# Sheet1.net
KiCad netlist of a schematic drawn in Altium Designer
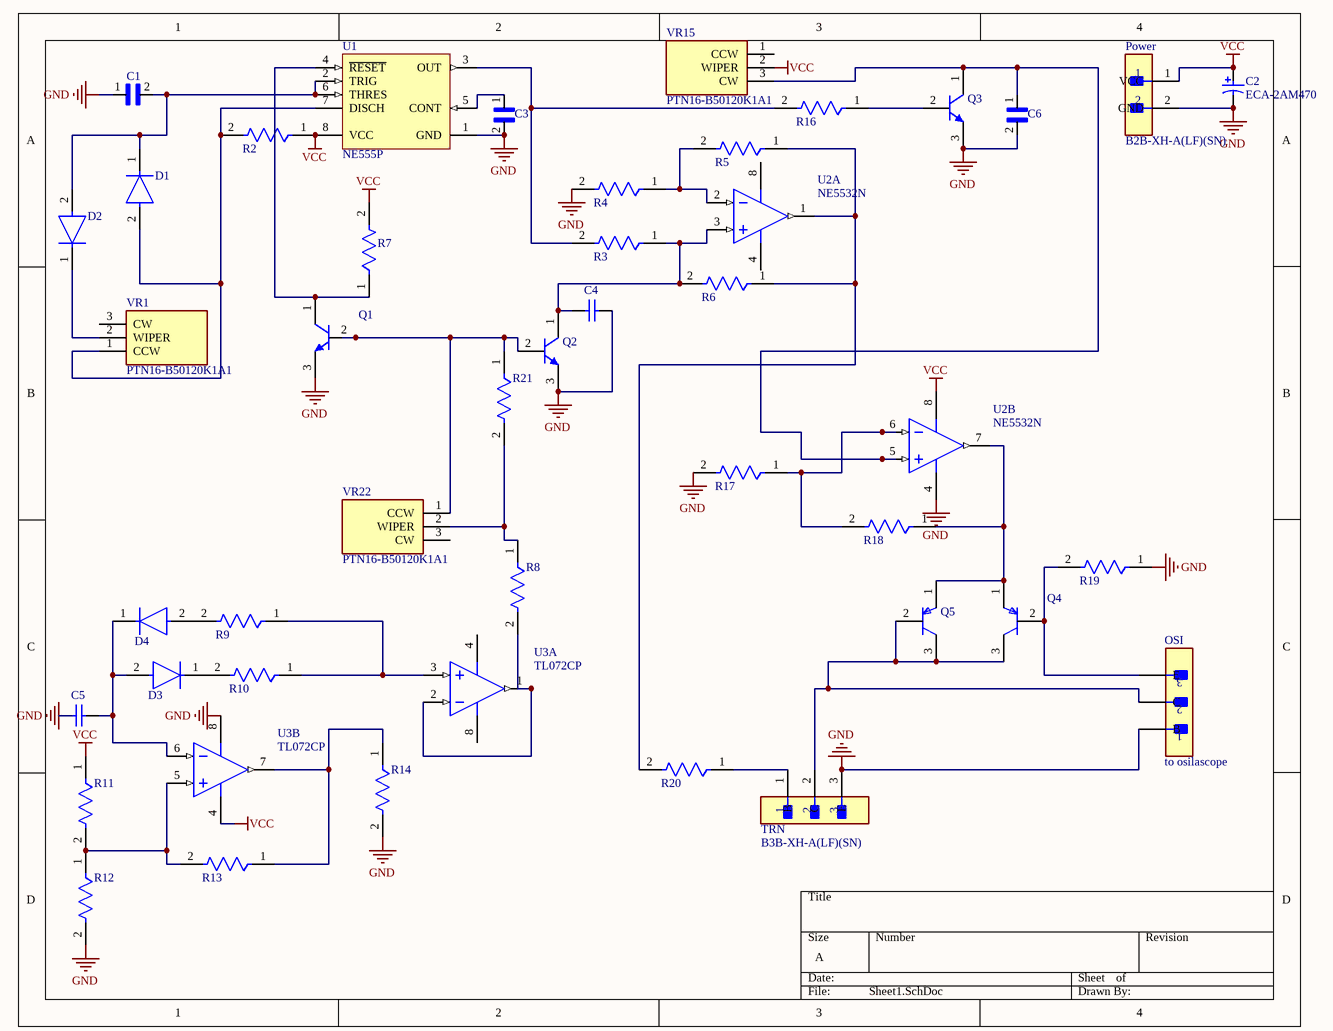
[diagram p0: Sheet1.SchDoc]

(export (version "E")
  (design (tool "Eeschema 10.0.6"))
  (components
    (comp (ref "C1")
      (value "FG24X7R1A106KRT00")
      (footprint "CAPRB500W50L450T300H550")
      (description "10 ÂµF Â±10% 10V Ceramic Capacitor X7R Radial")
      (fields (field (name "MF") "TDK"))
      (libsource (lib "") (part "FG24X7R1A106KRT00_1"))
    )
    (comp (ref "C2")
      (value "ECA-2AM470")
      (footprint "CAPPR65-350-1150X800X1250")
      (description "Aluminum Electrolytic Capacitor, 47 uF, +/- 20%, 100 V, -40 to 85 degC, 2-Pin THD, RoHS, Bulk")
      (libsource (lib "Altium Content Vault") (part "CAP-P-2"))
    )
    (comp (ref "C3")
      (value "FG24X7R1A106KRT00")
      (footprint "CAPRB500W50L450T300H550")
      (description "10 ÂµF Â±10% 10V Ceramic Capacitor X7R Radial")
      (fields (field (name "MF") "TDK"))
      (libsource (lib "FG24X7R1A106KRT00") (part "FG24X7R1A106KRT00"))
    )
    (comp (ref "C4")
      (value "SA115C104KAR")
      (footprint "AVX-SA115C104KAR")
      (fields (field (name "TOLERANCE") "±10%") (field (name "MANUFACTURER") "AVX"))
      (libsource (lib "Altium Content Vault") (part "CAP-NP-2"))
    )
    (comp (ref "C5")
      (value "SA115C104KAR")
      (footprint "AVX-SA115C104KAR")
      (fields (field (name "TOLERANCE") "±10%") (field (name "MANUFACTURER") "AVX"))
      (libsource (lib "Altium Content Vault") (part "CAP-NP-2"))
    )
    (comp (ref "C6")
      (value "FG24X7R1A106KRT00")
      (footprint "CAPRB500W50L450T300H550")
      (description "10 ÂµF Â±10% 10V Ceramic Capacitor X7R Radial")
      (fields (field (name "MF") "TDK"))
      (libsource (lib "FG24X7R1A106KRT00") (part "FG24X7R1A106KRT00"))
    )
    (comp (ref "D1")
      (value "1N4001-E3/54")
      (footprint "FP-1N4001-E3-54-MFG")
      (description "DIODE GEN PURP 50V 1A DO204AL")
      (fields (field (name "VOLTAGE") "50V"))
      (libsource (lib "Altium Content Vault") (part "d7152d700b627762746794eb795d46e"))
    )
    (comp (ref "D2")
      (value "1N4001-E3/54")
      (footprint "FP-1N4001-E3-54-MFG")
      (description "DIODE GEN PURP 50V 1A DO204AL")
      (fields (field (name "VOLTAGE") "50V"))
      (libsource (lib "Altium Content Vault") (part "d7152d700b627762746794eb795d46e"))
    )
    (comp (ref "D3")
      (value "1N4001-E3/54")
      (footprint "FP-1N4001-E3-54-MFG")
      (description "DIODE GEN PURP 50V 1A DO204AL")
      (fields (field (name "VOLTAGE") "50V"))
      (libsource (lib "Altium Content Vault") (part "d7152d700b627762746794eb795d46e"))
    )
    (comp (ref "D4")
      (value "1N4001-E3/54")
      (footprint "FP-1N4001-E3-54-MFG")
      (description "DIODE GEN PURP 50V 1A DO204AL")
      (fields (field (name "VOLTAGE") "50V"))
      (libsource (lib "Altium Content Vault") (part "d7152d700b627762746794eb795d46e"))
    )
    (comp (ref "OSI")
      (value "to osilascope")
      (footprint "FP-B3B-XH-A_LF_SN-MFG")
      (description "CONN HEADER VERT 3POS 2.5MM")
      (libsource (lib "Altium Content Vault") (part "0d3f023dd272f625e17a2be33dea85f"))
    )
    (comp (ref "Power")
      (value "B2B-XH-A(LF)(SN)")
      (footprint "FP-B2B-XH-A_LF_SN-MFG")
      (description "CONN HEADER VERT 2POS 2.5MM")
      (libsource (lib "Altium Content Vault") (part "3bc925449376181038e59eaffc5286c"))
    )
    (comp (ref "Q1")
      (value "P2N2222ARL1G")
      (footprint "ONSC-TO-92-3-29-11_AM_BL")
      (description "Amplifier Transistor, NPN Silicon, 3-Pin TO-92, Pb-Free, Tape and Reel")
      (fields (field (name "MANUFACTURER") "On Semiconductor"))
      (libsource (lib "Altium Content Vault") (part "ONSC-NPN-C1B2E3-3"))
    )
    (comp (ref "Q2")
      (value "P2N2222ARL1G")
      (footprint "ONSC-TO-92-3-29-11_AM_BL")
      (description "Amplifier Transistor, NPN Silicon, 3-Pin TO-92, Pb-Free, Tape and Reel")
      (fields (field (name "MANUFACTURER") "On Semiconductor"))
      (libsource (lib "Altium Content Vault") (part "ONSC-NPN-C1B2E3-3"))
    )
    (comp (ref "Q3")
      (value "P2N2222ARL1G")
      (footprint "ONSC-TO-92-3-29-11_AM_BL")
      (description "Amplifier Transistor, NPN Silicon, 3-Pin TO-92, Pb-Free, Tape and Reel")
      (fields (field (name "MANUFACTURER") "On Semiconductor"))
      (libsource (lib "Altium Content Vault") (part "ONSC-NPN-C1B2E3-3"))
    )
    (comp (ref "Q4")
      (value "2N3906TF")
      (footprint "FP-135AR-MFG")
      (description "2N3906TF Small Signal Bipolar Transistor, 0.2A I(C), 40V V(BR)CEO, 1-Element, PNP, Silicon, TO-92")
      (libsource (lib "Altium Content Vault") (part "40d2b7e180a7bcff784209620afba3e"))
    )
    (comp (ref "Q5")
      (value "2N3906TF")
      (footprint "FP-135AR-MFG")
      (description "2N3906TF Small Signal Bipolar Transistor, 0.2A I(C), 40V V(BR)CEO, 1-Element, PNP, Silicon, TO-92")
      (libsource (lib "Altium Content Vault") (part "40d2b7e180a7bcff784209620afba3e"))
    )
    (comp (ref "R2")
      (value "MRS16000C2002FCT00")
      (footprint "FP-MRS1600-MFG")
      (description "RES 20K OHM 0.4W 1% AXIAL")
      (fields (field (name "TOLERANCE") "1%"))
      (libsource (lib "Altium Content Vault") (part "1029c3af85768c4190bb7ad29bc67b5"))
    )
    (comp (ref "R3")
      (value "MRS16000C2002FCT00")
      (footprint "FP-MRS1600-MFG")
      (description "RES 20K OHM 0.4W 1% AXIAL")
      (fields (field (name "TOLERANCE") "1%"))
      (libsource (lib "Altium Content Vault") (part "1029c3af85768c4190bb7ad29bc67b5"))
    )
    (comp (ref "R4")
      (value "MRS16000C2002FCT00")
      (footprint "FP-MRS1600-MFG")
      (description "RES 20K OHM 0.4W 1% AXIAL")
      (fields (field (name "TOLERANCE") "1%"))
      (libsource (lib "Altium Content Vault") (part "1029c3af85768c4190bb7ad29bc67b5"))
    )
    (comp (ref "R5")
      (value "MRS16000C2002FCT00")
      (footprint "FP-MRS1600-MFG")
      (description "RES 20K OHM 0.4W 1% AXIAL")
      (fields (field (name "TOLERANCE") "1%"))
      (libsource (lib "Altium Content Vault") (part "1029c3af85768c4190bb7ad29bc67b5"))
    )
    (comp (ref "R6")
      (value "MRS16000C2002FCT00")
      (footprint "FP-MRS1600-MFG")
      (description "RES 20K OHM 0.4W 1% AXIAL")
      (fields (field (name "TOLERANCE") "1%"))
      (libsource (lib "Altium Content Vault") (part "1029c3af85768c4190bb7ad29bc67b5"))
    )
    (comp (ref "R7")
      (value "MRS16000C2002FCT00")
      (footprint "FP-MRS1600-MFG")
      (description "RES 20K OHM 0.4W 1% AXIAL")
      (fields (field (name "TOLERANCE") "1%"))
      (libsource (lib "Altium Content Vault") (part "1029c3af85768c4190bb7ad29bc67b5"))
    )
    (comp (ref "R8")
      (value "MRS16000C2002FCT00")
      (footprint "FP-MRS1600-MFG")
      (description "RES 20K OHM 0.4W 1% AXIAL")
      (fields (field (name "TOLERANCE") "1%"))
      (libsource (lib "Altium Content Vault") (part "1029c3af85768c4190bb7ad29bc67b5"))
    )
    (comp (ref "R9")
      (value "MRS16000C2002FCT00")
      (footprint "FP-MRS1600-MFG")
      (description "RES 20K OHM 0.4W 1% AXIAL")
      (fields (field (name "TOLERANCE") "1%"))
      (libsource (lib "Altium Content Vault") (part "1029c3af85768c4190bb7ad29bc67b5"))
    )
    (comp (ref "R10")
      (value "MRS16000C2002FCT00")
      (footprint "FP-MRS1600-MFG")
      (description "RES 20K OHM 0.4W 1% AXIAL")
      (fields (field (name "TOLERANCE") "1%"))
      (libsource (lib "Altium Content Vault") (part "1029c3af85768c4190bb7ad29bc67b5"))
    )
    (comp (ref "R11")
      (value "MRS16000C2002FCT00")
      (footprint "FP-MRS1600-MFG")
      (description "RES 20K OHM 0.4W 1% AXIAL")
      (fields (field (name "TOLERANCE") "1%"))
      (libsource (lib "Altium Content Vault") (part "1029c3af85768c4190bb7ad29bc67b5"))
    )
    (comp (ref "R12")
      (value "MRS16000C2002FCT00")
      (footprint "FP-MRS1600-MFG")
      (description "RES 20K OHM 0.4W 1% AXIAL")
      (fields (field (name "TOLERANCE") "1%"))
      (libsource (lib "Altium Content Vault") (part "1029c3af85768c4190bb7ad29bc67b5"))
    )
    (comp (ref "R13")
      (value "MRS16000C2002FCT00")
      (footprint "FP-MRS1600-MFG")
      (description "RES 20K OHM 0.4W 1% AXIAL")
      (fields (field (name "TOLERANCE") "1%"))
      (libsource (lib "Altium Content Vault") (part "1029c3af85768c4190bb7ad29bc67b5"))
    )
    (comp (ref "R14")
      (value "MRS16000C2002FCT00")
      (footprint "FP-MRS1600-MFG")
      (description "RES 20K OHM 0.4W 1% AXIAL")
      (fields (field (name "TOLERANCE") "1%"))
      (libsource (lib "Altium Content Vault") (part "1029c3af85768c4190bb7ad29bc67b5"))
    )
    (comp (ref "R16")
      (value "MRS16000C2002FCT00")
      (footprint "FP-MRS1600-MFG")
      (description "RES 20K OHM 0.4W 1% AXIAL")
      (fields (field (name "TOLERANCE") "1%"))
      (libsource (lib "Altium Content Vault") (part "1029c3af85768c4190bb7ad29bc67b5"))
    )
    (comp (ref "R17")
      (value "MRS16000C2002FCT00")
      (footprint "FP-MRS1600-MFG")
      (description "RES 20K OHM 0.4W 1% AXIAL")
      (fields (field (name "TOLERANCE") "1%"))
      (libsource (lib "Altium Content Vault") (part "1029c3af85768c4190bb7ad29bc67b5"))
    )
    (comp (ref "R18")
      (value "MRS16000C2002FCT00")
      (footprint "FP-MRS1600-MFG")
      (description "RES 20K OHM 0.4W 1% AXIAL")
      (fields (field (name "TOLERANCE") "1%"))
      (libsource (lib "Altium Content Vault") (part "1029c3af85768c4190bb7ad29bc67b5"))
    )
    (comp (ref "R19")
      (value "MRS16000C2002FCT00")
      (footprint "FP-MRS1600-MFG")
      (description "RES 20K OHM 0.4W 1% AXIAL")
      (fields (field (name "TOLERANCE") "1%"))
      (libsource (lib "Altium Content Vault") (part "1029c3af85768c4190bb7ad29bc67b5"))
    )
    (comp (ref "R20")
      (value "MRS16000C2002FCT00")
      (footprint "FP-MRS1600-MFG")
      (description "RES 20K OHM 0.4W 1% AXIAL")
      (fields (field (name "TOLERANCE") "1%"))
      (libsource (lib "Altium Content Vault") (part "1029c3af85768c4190bb7ad29bc67b5"))
    )
    (comp (ref "R21")
      (value "MRS16000C2002FCT00")
      (footprint "FP-MRS1600-MFG")
      (description "RES 20K OHM 0.4W 1% AXIAL")
      (fields (field (name "TOLERANCE") "1%"))
      (libsource (lib "Altium Content Vault") (part "1029c3af85768c4190bb7ad29bc67b5"))
    )
    (comp (ref "TRN")
      (value "B3B-XH-A(LF)(SN)")
      (footprint "FP-B3B-XH-A_LF_SN-MFG")
      (description "CONN HEADER VERT 3POS 2.5MM")
      (libsource (lib "") (part "0d3f023dd272f625e17a2be33dea85f_1"))
    )
    (comp (ref "U1")
      (value "NE555P")
      (footprint "P0008A")
      (description "Precision Timer, 4.5 to 16 V, 0 to 70 degC, 8-Pin DIP, Pb-Free, Tube")
      (fields (field (name "MANUFACTURER") "TexasInstruments"))
      (libsource (lib "Altium Content Vault") (part "TI-NE555-P8"))
    )
    (comp (ref "U2")
      (value "NE5532N")
      (footprint "ONSC-PDIP-8-626-05")
      (fields (field (name "MANUFACTURER") "On Semiconductor"))
      (libsource (lib "Altium Content Vault") (part "ONSC-NE5532-PDIP-8-626-05"))
    )
    (comp (ref "U3")
      (value "TL072CP")
      (footprint "P0008A")
      (fields (field (name "MANUFACTURER") "Texas Instruments"))
      (libsource (lib "Altium Content Vault") (part "TI-AMP-D6-2-8_D"))
    )
    (comp (ref "VR1")
      (value "PTN16-B50120K1A1")
      (footprint "SamacSys:PTN16B50120K1A1")
      (description "Variable Resistor")
      (libsource (lib "") (part "PTN16-B50120K1A1_1"))
    )
    (comp (ref "VR15")
      (value "PTN16-B50120K1A1")
      (footprint "SamacSys:PTN16B50120K1A1")
      (description "Variable Resistor")
      (libsource (lib "*") (part "PTN16-B50120K1A1"))
    )
    (comp (ref "VR22")
      (value "PTN16-B50120K1A1")
      (footprint "SamacSys:PTN16B50120K1A1")
      (description "Variable Resistor")
      (libsource (lib "*") (part "PTN16-B50120K1A1"))
    )
  )
  (nets
    (net (code "1") (name "GND") (class "Default")
      (node (ref "C1") (pin "1") (pinfunction "1_1") (pintype "passive"))
      (node (ref "C2") (pin "2") (pinfunction "2_2") (pintype "passive"))
      (node (ref "C3") (pin "2") (pinfunction "2_2") (pintype "passive"))
      (node (ref "C4") (pin "2") (pinfunction "2_2") (pintype "passive"))
      (node (ref "C5") (pin "1") (pinfunction "1_1") (pintype "passive"))
      (node (ref "C6") (pin "2") (pinfunction "2_2") (pintype "passive"))
      (node (ref "OSI") (pin "1") (pinfunction "B_1") (pintype "passive"))
      (node (ref "Power") (pin "2") (pinfunction "GND_2") (pintype "passive"))
      (node (ref "Q1") (pin "3") (pinfunction "E_3") (pintype "passive"))
      (node (ref "Q2") (pin "3") (pinfunction "E_3") (pintype "passive"))
      (node (ref "Q3") (pin "3") (pinfunction "E_3") (pintype "passive"))
      (node (ref "R12") (pin "2") (pinfunction "2_2") (pintype "passive"))
      (node (ref "R14") (pin "2") (pinfunction "2_2") (pintype "passive"))
      (node (ref "R17") (pin "2") (pinfunction "2_2") (pintype "passive"))
      (node (ref "R19") (pin "1") (pinfunction "1_1") (pintype "passive"))
      (node (ref "R4") (pin "2") (pinfunction "2_2") (pintype "passive"))
      (node (ref "TRN") (pin "3") (pinfunction "E_3") (pintype "passive"))
      (node (ref "U1") (pin "1") (pinfunction "GND_1") (pintype "power_in"))
      (node (ref "U2") (pin "4") (pinfunction "V-_4") (pintype "power_in"))
      (node (ref "U3") (pin "8") (pinfunction "VCC+_8") (pintype "power_in"))
    )
    (net (code "2") (name "Net-(D1-A)") (class "Default")
      (node (ref "D1") (pin "2") (pinfunction "A_2") (pintype "passive"))
      (node (ref "R2") (pin "2") (pinfunction "2_2") (pintype "passive"))
      (node (ref "U1") (pin "7") (pinfunction "DISCH_7") (pintype "open_collector"))
      (node (ref "VR1") (pin "1") (pinfunction "CCW_1") (pintype "passive"))
    )
    (net (code "3") (name "Net-(D1-C)") (class "Default")
      (node (ref "C1") (pin "2") (pinfunction "2_2") (pintype "passive"))
      (node (ref "D1") (pin "1") (pinfunction "C_1") (pintype "passive"))
      (node (ref "D2") (pin "2") (pinfunction "A_2") (pintype "passive"))
      (node (ref "U1") (pin "2") (pinfunction "TRIG_2") (pintype "input"))
      (node (ref "U1") (pin "6") (pinfunction "THRES_6") (pintype "input"))
    )
    (net (code "4") (name "Net-(D2-C)") (class "Default")
      (node (ref "D2") (pin "1") (pinfunction "C_1") (pintype "passive"))
      (node (ref "VR1") (pin "2") (pinfunction "WIPER_2") (pintype "passive"))
    )
    (net (code "5") (name "Net-(D3-A)") (class "Default")
      (node (ref "C5") (pin "2") (pinfunction "2_2") (pintype "passive"))
      (node (ref "D3") (pin "2") (pinfunction "A_2") (pintype "passive"))
      (node (ref "D4") (pin "1") (pinfunction "C_1") (pintype "passive"))
      (node (ref "U3") (pin "6") (pinfunction "IN2-_6") (pintype "input"))
    )
    (net (code "6") (name "Net-(D3-C)") (class "Default")
      (node (ref "D3") (pin "1") (pinfunction "C_1") (pintype "passive"))
      (node (ref "R10") (pin "2") (pinfunction "2_2") (pintype "passive"))
    )
    (net (code "7") (name "Net-(D4-A)") (class "Default")
      (node (ref "D4") (pin "2") (pinfunction "A_2") (pintype "passive"))
      (node (ref "R9") (pin "2") (pinfunction "2_2") (pintype "passive"))
    )
    (net (code "8") (name "Net-(OSI-C)") (class "Default")
      (node (ref "OSI") (pin "2") (pinfunction "C_2") (pintype "passive"))
      (node (ref "Q4") (pin "3") (pinfunction "C_3") (pintype "passive"))
      (node (ref "Q5") (pin "2") (pinfunction "B_2") (pintype "passive"))
      (node (ref "Q5") (pin "3") (pinfunction "C_3") (pintype "passive"))
      (node (ref "TRN") (pin "2") (pinfunction "C_2") (pintype "passive"))
    )
    (net (code "9") (name "Net-(OSI-E)") (class "Default")
      (node (ref "OSI") (pin "3") (pinfunction "E_3") (pintype "passive"))
      (node (ref "Q4") (pin "2") (pinfunction "B_2") (pintype "passive"))
      (node (ref "R19") (pin "2") (pinfunction "2_2") (pintype "passive"))
    )
    (net (code "10") (name "Net-(Q1-B)") (class "Default")
      (node (ref "Q1") (pin "2") (pinfunction "B_2") (pintype "passive"))
      (node (ref "Q2") (pin "2") (pinfunction "B_2") (pintype "passive"))
      (node (ref "R21") (pin "1") (pinfunction "1_1") (pintype "passive"))
      (node (ref "VR22") (pin "1") (pinfunction "CCW_1") (pintype "passive"))
    )
    (net (code "11") (name "Net-(Q1-C)") (class "Default")
      (node (ref "Q1") (pin "1") (pinfunction "C_1") (pintype "passive"))
      (node (ref "R7") (pin "1") (pinfunction "1_1") (pintype "passive"))
      (node (ref "U1") (pin "4") (pinfunction "~{RESET}_4") (pintype "input"))
    )
    (net (code "12") (name "Net-(Q2-C)") (class "Default")
      (node (ref "C4") (pin "1") (pinfunction "1_1") (pintype "passive"))
      (node (ref "Q2") (pin "1") (pinfunction "C_1") (pintype "passive"))
      (node (ref "R3") (pin "1") (pinfunction "1_1") (pintype "passive"))
      (node (ref "R6") (pin "2") (pinfunction "2_2") (pintype "passive"))
      (node (ref "U2") (pin "3") (pinfunction "INA+_3") (pintype "input"))
    )
    (net (code "13") (name "Net-(Q3-B)") (class "Default")
      (node (ref "Q3") (pin "2") (pinfunction "B_2") (pintype "passive"))
      (node (ref "R16") (pin "1") (pinfunction "1_1") (pintype "passive"))
    )
    (net (code "14") (name "Net-(Q3-C)") (class "Default")
      (node (ref "C6") (pin "1") (pinfunction "1_1") (pintype "passive"))
      (node (ref "Q3") (pin "1") (pinfunction "C_1") (pintype "passive"))
      (node (ref "U2") (pin "5") (pinfunction "INB+_5") (pintype "input"))
      (node (ref "VR15") (pin "3") (pinfunction "CW_3") (pintype "passive"))
    )
    (net (code "15") (name "Net-(Q4-E)") (class "Default")
      (node (ref "Q4") (pin "1") (pinfunction "E_1") (pintype "passive"))
      (node (ref "Q5") (pin "1") (pinfunction "E_1") (pintype "passive"))
      (node (ref "R18") (pin "1") (pinfunction "1_1") (pintype "passive"))
      (node (ref "U2") (pin "7") (pinfunction "OUTB_7") (pintype "output"))
    )
    (net (code "16") (name "Net-(TRN-B)") (class "Default")
      (node (ref "R20") (pin "1") (pinfunction "1_1") (pintype "passive"))
      (node (ref "TRN") (pin "1") (pinfunction "B_1") (pintype "passive"))
    )
    (net (code "17") (name "Net-(U1-CONT)") (class "Default")
      (node (ref "C3") (pin "1") (pinfunction "1_1") (pintype "passive"))
      (node (ref "U1") (pin "5") (pinfunction "CONT_5") (pintype "input"))
    )
    (net (code "18") (name "Net-(U1-OUT)") (class "Default")
      (node (ref "R16") (pin "2") (pinfunction "2_2") (pintype "passive"))
      (node (ref "R3") (pin "2") (pinfunction "2_2") (pintype "passive"))
      (node (ref "U1") (pin "3") (pinfunction "OUT_3") (pintype "output"))
    )
    (net (code "19") (name "Net-(U2A-INA-)") (class "Default")
      (node (ref "R4") (pin "1") (pinfunction "1_1") (pintype "passive"))
      (node (ref "R5") (pin "2") (pinfunction "2_2") (pintype "passive"))
      (node (ref "U2") (pin "2") (pinfunction "INA-_2") (pintype "input"))
    )
    (net (code "20") (name "Net-(U2A-OUTA)") (class "Default")
      (node (ref "R20") (pin "2") (pinfunction "2_2") (pintype "passive"))
      (node (ref "R5") (pin "1") (pinfunction "1_1") (pintype "passive"))
      (node (ref "R6") (pin "1") (pinfunction "1_1") (pintype "passive"))
      (node (ref "U2") (pin "1") (pinfunction "OUTA_1") (pintype "output"))
    )
    (net (code "21") (name "Net-(U2B-INB-)") (class "Default")
      (node (ref "R17") (pin "1") (pinfunction "1_1") (pintype "passive"))
      (node (ref "R18") (pin "2") (pinfunction "2_2") (pintype "passive"))
      (node (ref "U2") (pin "6") (pinfunction "INB-_6") (pintype "input"))
    )
    (net (code "22") (name "Net-(U3A-IN1+)") (class "Default")
      (node (ref "R10") (pin "1") (pinfunction "1_1") (pintype "passive"))
      (node (ref "R9") (pin "1") (pinfunction "1_1") (pintype "passive"))
      (node (ref "U3") (pin "3") (pinfunction "IN1+_3") (pintype "input"))
    )
    (net (code "23") (name "Net-(U3A-IN1-)") (class "Default")
      (node (ref "R8") (pin "2") (pinfunction "2_2") (pintype "passive"))
      (node (ref "U3") (pin "1") (pinfunction "OUT1_1") (pintype "output"))
      (node (ref "U3") (pin "2") (pinfunction "IN1-_2") (pintype "input"))
    )
    (net (code "24") (name "Net-(U3B-IN2+)") (class "Default")
      (node (ref "R11") (pin "2") (pinfunction "2_2") (pintype "passive"))
      (node (ref "R12") (pin "1") (pinfunction "1_1") (pintype "passive"))
      (node (ref "R13") (pin "2") (pinfunction "2_2") (pintype "passive"))
      (node (ref "U3") (pin "5") (pinfunction "IN2+_5") (pintype "input"))
    )
    (net (code "25") (name "Net-(U3B-OUT2)") (class "Default")
      (node (ref "R13") (pin "1") (pinfunction "1_1") (pintype "passive"))
      (node (ref "R14") (pin "1") (pinfunction "1_1") (pintype "passive"))
      (node (ref "U3") (pin "7") (pinfunction "OUT2_7") (pintype "output"))
    )
    (net (code "26") (name "Net-(VR22-WIPER)") (class "Default")
      (node (ref "R21") (pin "2") (pinfunction "2_2") (pintype "passive"))
      (node (ref "R8") (pin "1") (pinfunction "1_1") (pintype "passive"))
      (node (ref "VR22") (pin "2") (pinfunction "WIPER_2") (pintype "passive"))
    )
    (net (code "27") (name "VCC") (class "Default")
      (node (ref "C2") (pin "1") (pinfunction "1_1") (pintype "passive"))
      (node (ref "Power") (pin "1") (pinfunction "VCC_1") (pintype "passive"))
      (node (ref "R11") (pin "1") (pinfunction "1_1") (pintype "passive"))
      (node (ref "R2") (pin "1") (pinfunction "1_1") (pintype "passive"))
      (node (ref "R7") (pin "2") (pinfunction "2_2") (pintype "passive"))
      (node (ref "U1") (pin "8") (pinfunction "VCC_8") (pintype "power_in"))
      (node (ref "U2") (pin "8") (pinfunction "V+_8") (pintype "power_in"))
      (node (ref "U3") (pin "4") (pinfunction "VCC-_4") (pintype "power_in"))
      (node (ref "VR15") (pin "2") (pinfunction "WIPER_2") (pintype "passive"))
    )
    (net (code "28") (name "unconnected-(U2A-V+-Pad8)") (class "Default")
      (node (ref "U2") (pin "8") (pinfunction "V+_8") (pintype "power_in"))
    )
    (net (code "29") (name "unconnected-(U2A-V--Pad4)") (class "Default")
      (node (ref "U2") (pin "4") (pinfunction "V-_4") (pintype "power_in"))
    )
    (net (code "30") (name "unconnected-(U3A-VCC+-Pad8)") (class "Default")
      (node (ref "U3") (pin "8") (pinfunction "VCC+_8") (pintype "power_in"))
    )
    (net (code "31") (name "unconnected-(U3A-VCC--Pad4)") (class "Default")
      (node (ref "U3") (pin "4") (pinfunction "VCC-_4") (pintype "power_in"))
    )
    (net (code "32") (name "unconnected-(VR1-CW-Pad3)") (class "Default")
      (node (ref "VR1") (pin "3") (pinfunction "CW_3") (pintype "passive"))
    )
    (net (code "33") (name "unconnected-(VR15-CCW-Pad1)") (class "Default")
      (node (ref "VR15") (pin "1") (pinfunction "CCW_1") (pintype "passive"))
    )
    (net (code "34") (name "unconnected-(VR22-CW-Pad3)") (class "Default")
      (node (ref "VR22") (pin "3") (pinfunction "CW_3") (pintype "passive"))
    )
  )
)
